# wifi.net
KiCad netlist of a schematic drawn in Altium Designer
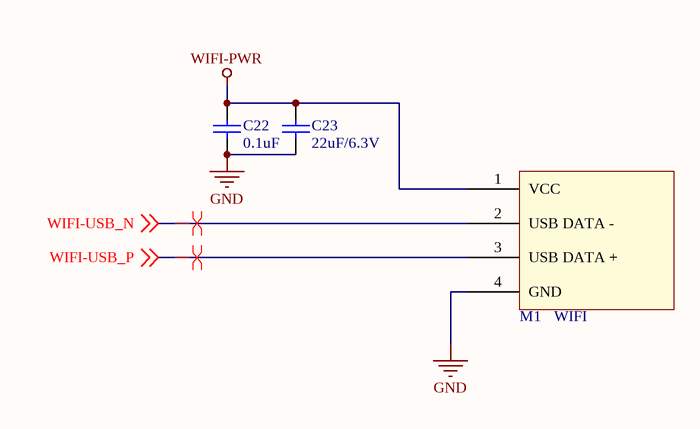
[diagram p0: wifi.SchDoc]

(export (version "E")
  (design (tool "Eeschema 10.0.6"))
  (components
    (comp (ref "C22")
      (value "0.1uF")
      (footprint "0603")
      (description "Capacitor")
      (libsource (lib "Miscellaneous Devices") (part "Cap"))
    )
    (comp (ref "C23")
      (value "22uF/6.3V")
      (footprint "0805")
      (description "Capacitor")
      (libsource (lib "Miscellaneous Devices") (part "Cap"))
    )
    (comp (ref "M1") (value "WIFI") (footprint "WIFI") (libsource (lib "Schlib") (part "WIFI")))
  )
  (nets
    (net (code "1") (name "GND") (class "Default")
      (node (ref "C22") (pin "2") (pinfunction "2_2") (pintype "passive"))
      (node (ref "C23") (pin "2") (pinfunction "2_2") (pintype "passive"))
      (node (ref "M1") (pin "4") (pinfunction "GND_4") (pintype "passive"))
    )
    (net (code "2") (name "WIFI-PWR") (class "Default")
      (node (ref "C22") (pin "1") (pinfunction "1_1") (pintype "passive"))
      (node (ref "C23") (pin "1") (pinfunction "1_1") (pintype "passive"))
      (node (ref "M1") (pin "1") (pinfunction "VCC_1") (pintype "passive"))
    )
    (net (code "3") (name "WIFI-USB_N") (class "Default")
      (node (ref "M1") (pin "2") (pinfunction "USB_DATA_-_2") (pintype "passive"))
    )
    (net (code "4") (name "WIFI-USB_P") (class "Default")
      (node (ref "M1") (pin "3") (pinfunction "USB_DATA_+_3") (pintype "passive"))
    )
  )
)
